# Ethernet_Mini_Shield_v0_1.net
KiCad netlist of a schematic drawn in EAGLE
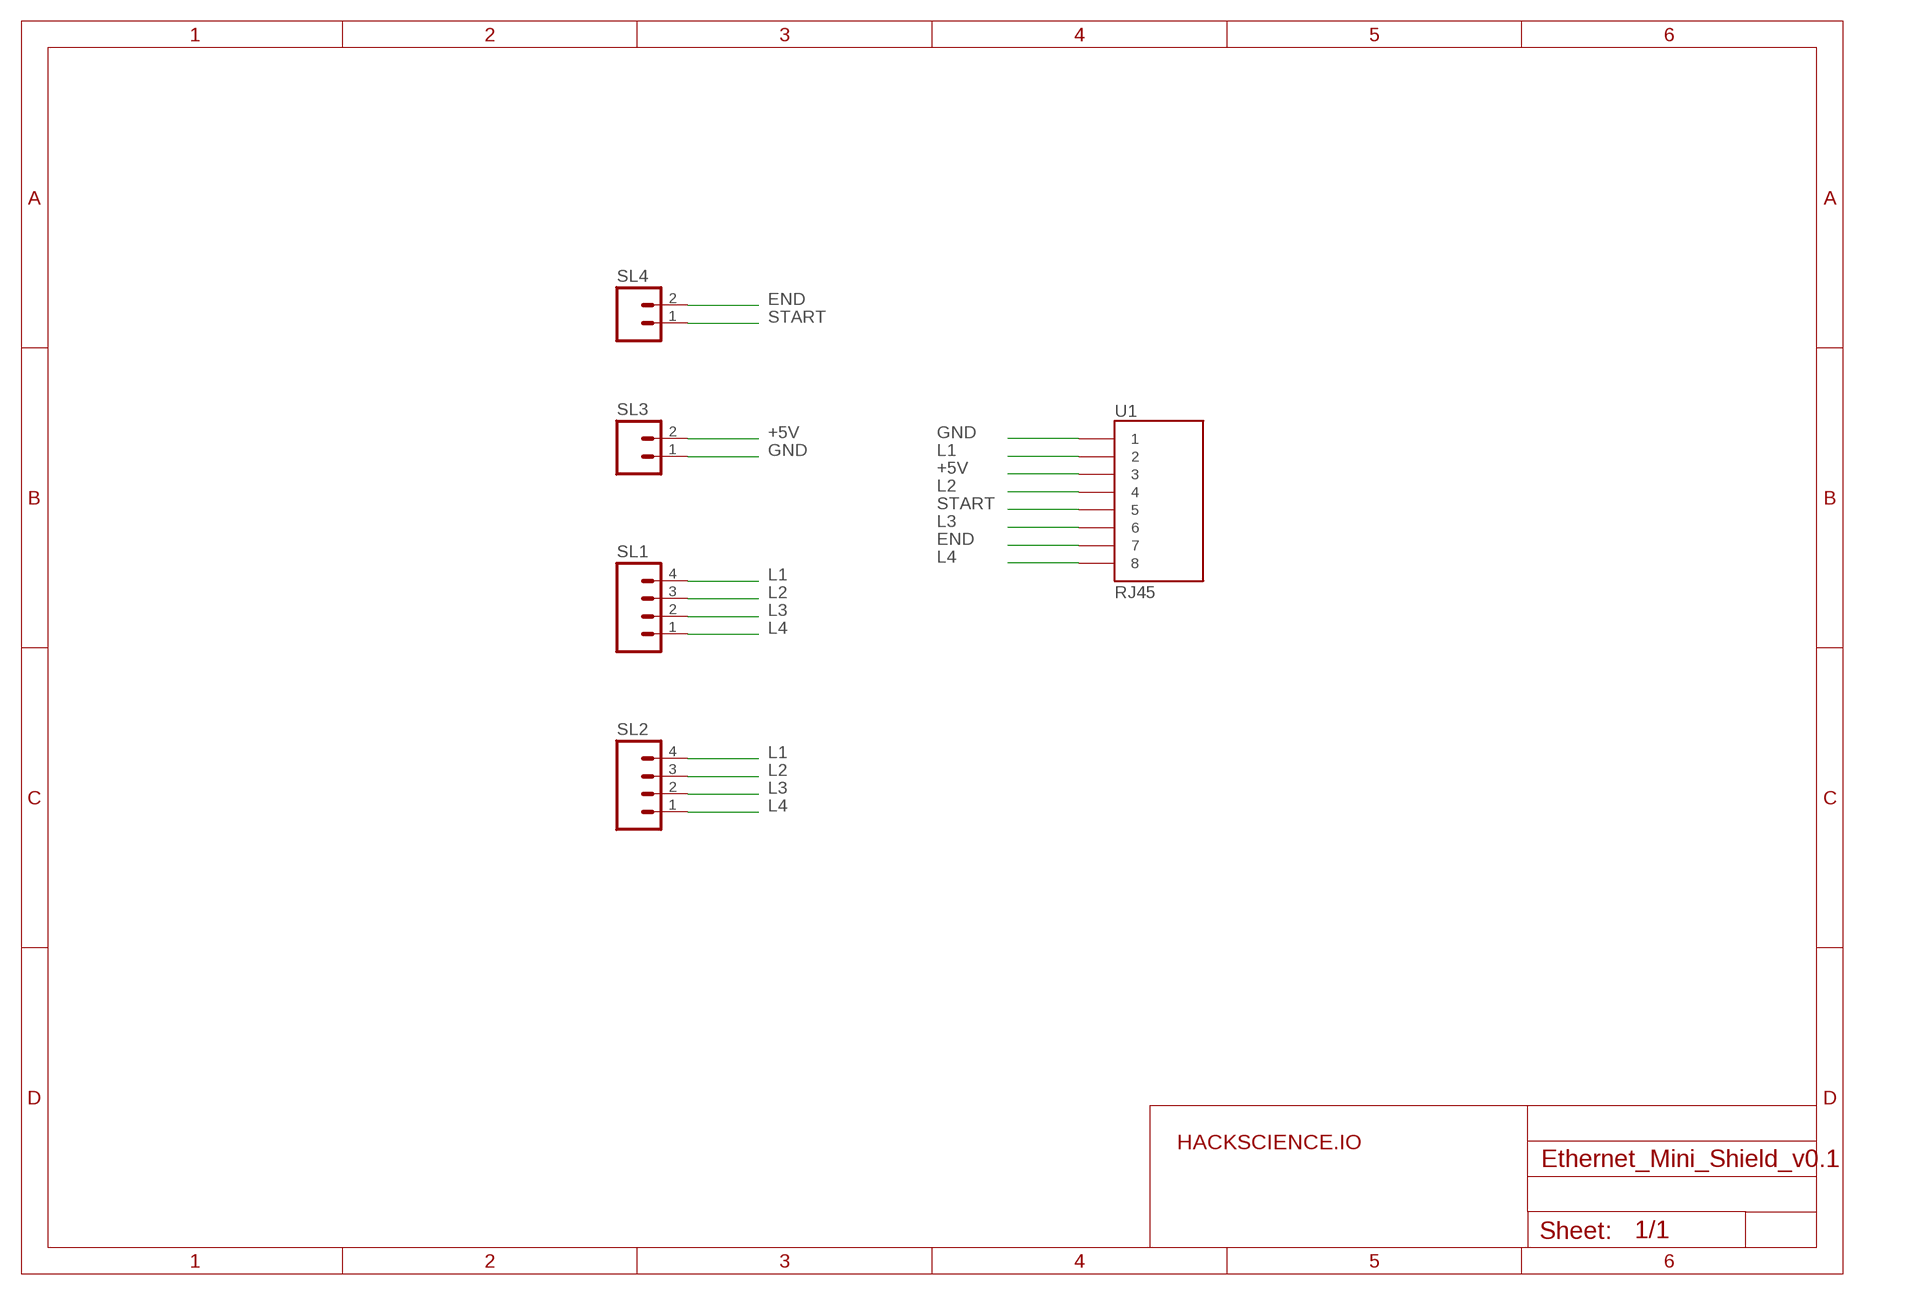
[diagram p0: schematic, sheet 1]

(export (version "E")
  (design (tool "Eeschema 10.0.6"))
  (components
    (comp (ref "SL1")
      (value "M04")
      (footprint "eagle-import:04P")
      (libsource (lib "eagle-import") (part "M04"))
    )
    (comp (ref "SL2")
      (value "M04")
      (footprint "eagle-import:04P")
      (libsource (lib "eagle-import") (part "M04"))
    )
    (comp (ref "SL3")
      (value "M02")
      (footprint "eagle-import:02P")
      (libsource (lib "eagle-import") (part "M02"))
    )
    (comp (ref "SL4")
      (value "M02")
      (footprint "eagle-import:02P")
      (libsource (lib "eagle-import") (part "M02"))
    )
    (comp (ref "U1")
      (value "RJ45")
      (footprint "eagle-import:RJ45-8")
      (libsource (lib "eagle-import") (part "RJ45-8PTH"))
    )
  )
  (nets
    (net (code "1") (name "/+5V") (class "Default")
      (node (ref "SL3") (pin "2") (pinfunction "2_2") (pintype "passive"))
      (node (ref "U1") (pin "3") (pinfunction "3_3") (pintype "bidirectional"))
    )
    (net (code "2") (name "/END") (class "Default")
      (node (ref "SL4") (pin "2") (pinfunction "2_2") (pintype "passive"))
      (node (ref "U1") (pin "7") (pinfunction "7_7") (pintype "bidirectional"))
    )
    (net (code "3") (name "/GND") (class "Default")
      (node (ref "SL3") (pin "1") (pinfunction "1_1") (pintype "passive"))
      (node (ref "U1") (pin "1") (pinfunction "1_1") (pintype "bidirectional"))
    )
    (net (code "4") (name "/L1") (class "Default")
      (node (ref "SL1") (pin "4") (pinfunction "4_4") (pintype "passive"))
      (node (ref "SL2") (pin "4") (pinfunction "4_4") (pintype "passive"))
      (node (ref "U1") (pin "2") (pinfunction "2_2") (pintype "bidirectional"))
    )
    (net (code "5") (name "/L2") (class "Default")
      (node (ref "SL1") (pin "3") (pinfunction "3_3") (pintype "passive"))
      (node (ref "SL2") (pin "3") (pinfunction "3_3") (pintype "passive"))
      (node (ref "U1") (pin "4") (pinfunction "4_4") (pintype "bidirectional"))
    )
    (net (code "6") (name "/L3") (class "Default")
      (node (ref "SL1") (pin "2") (pinfunction "2_2") (pintype "passive"))
      (node (ref "SL2") (pin "2") (pinfunction "2_2") (pintype "passive"))
      (node (ref "U1") (pin "6") (pinfunction "6_6") (pintype "bidirectional"))
    )
    (net (code "7") (name "/L4") (class "Default")
      (node (ref "SL1") (pin "1") (pinfunction "1_1") (pintype "passive"))
      (node (ref "SL2") (pin "1") (pinfunction "1_1") (pintype "passive"))
      (node (ref "U1") (pin "8") (pinfunction "8_8") (pintype "bidirectional"))
    )
    (net (code "8") (name "/START") (class "Default")
      (node (ref "SL4") (pin "1") (pinfunction "1_1") (pintype "passive"))
      (node (ref "U1") (pin "5") (pinfunction "5_5") (pintype "bidirectional"))
    )
  )
)
